# Geiger.net
KiCad netlist of a schematic drawn in EAGLE
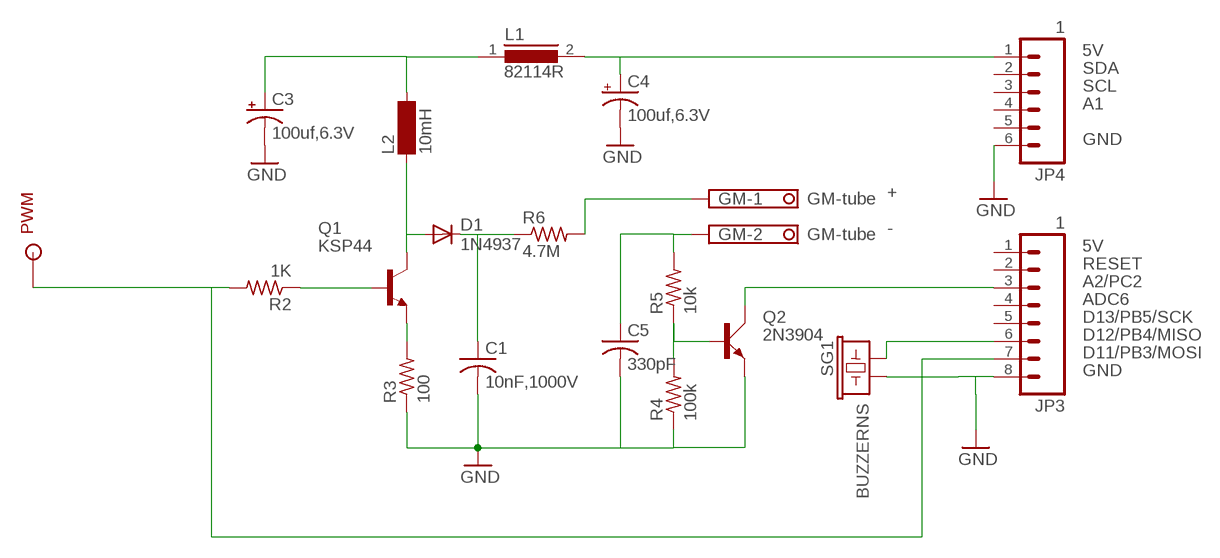
[diagram p0: schematic, sheet 1]

(export (version "E")
  (design (tool "Eeschema 10.0.6"))
  (components
    (comp (ref "C1")
      (value "10nF,1000V")
      (footprint "eagle-import:C150-054X183")
      (libsource (lib "eagle-import") (part "C-US150-054X183"))
    )
    (comp (ref "C3")
      (value "100uf,6.3V")
      (footprint "eagle-import:E2,5-7")
      (libsource (lib "eagle-import") (part "CPOL-USE2.5-7"))
    )
    (comp (ref "C4")
      (value "100uf,6.3V")
      (footprint "eagle-import:E2,5-7")
      (libsource (lib "eagle-import") (part "CPOL-USE2.5-7"))
    )
    (comp (ref "C5")
      (value "330pF")
      (footprint "eagle-import:C050-045X075")
      (libsource (lib "eagle-import") (part "C-US050-045X075"))
    )
    (comp (ref "D1")
      (value "1N4937")
      (footprint "eagle-import:DO41-10")
      (libsource (lib "eagle-import") (part "1N4933"))
    )
    (comp (ref "GM")
      (value "GM-tube")
      (footprint "eagle-import:1751248")
      (libsource (lib "eagle-import") (part "1751248"))
    )
    (comp (ref "JP3")
      (value "1")
      (footprint "eagle-import:1X08")
      (libsource (lib "eagle-import") (part "M081X08"))
    )
    (comp (ref "JP4")
      (value "1")
      (footprint "eagle-import:1X06")
      (libsource (lib "eagle-import") (part "M06SIP"))
    )
    (comp (ref "L1")
      (value "82114R")
      (footprint "eagle-import:82114R")
      (libsource (lib "eagle-import") (part "82114R"))
    )
    (comp (ref "L2")
      (value "10mH")
      (footprint "eagle-import:BS11")
      (libsource (lib "eagle-import") (part "BS11"))
    )
    (comp (ref "PWM")
      (value "SOLDER_POINTA")
      (footprint "eagle-import:P1-13")
      (libsource (lib "eagle-import") (part "SOLDER_POINTA"))
    )
    (comp (ref "Q1")
      (value "KSP44")
      (footprint "eagle-import:TO92-EBC")
      (libsource (lib "eagle-import") (part "BC550B"))
    )
    (comp (ref "Q2")
      (value "2N3904")
      (footprint "eagle-import:TO92D")
      (libsource (lib "eagle-import") (part "2N3904"))
    )
    (comp (ref "R2")
      (value "1K")
      (footprint "eagle-import:0207_10")
      (libsource (lib "eagle-import") (part "R-US_0207/10"))
    )
    (comp (ref "R3")
      (value "100")
      (footprint "eagle-import:0207_10")
      (libsource (lib "eagle-import") (part "R-US_0207/10"))
    )
    (comp (ref "R4")
      (value "100k")
      (footprint "eagle-import:0207_10")
      (libsource (lib "eagle-import") (part "R-US_0207/10"))
    )
    (comp (ref "R5")
      (value "10k")
      (footprint "eagle-import:0207_10")
      (libsource (lib "eagle-import") (part "R-US_0207/10"))
    )
    (comp (ref "R6")
      (value "4.7M")
      (footprint "eagle-import:0207_10")
      (libsource (lib "eagle-import") (part "R-US_0207/10"))
    )
    (comp (ref "SG1")
      (value "BUZZERNS")
      (footprint "eagle-import:BUZZER-12MM-NS")
      (libsource (lib "eagle-import") (part "BUZZERNS"))
    )
  )
  (nets
    (net (code "1") (name "/RESET") (class "Default")
      (node (ref "JP3") (pin "3") (pinfunction "3_3") (pintype "passive"))
      (node (ref "Q2") (pin "C") (pinfunction "C_C") (pintype "passive"))
    )
    (net (code "2") (name "GND") (class "Default")
      (node (ref "C1") (pin "2") (pinfunction "2_2") (pintype "passive"))
      (node (ref "C3") (pin "-") (pinfunction "-_-") (pintype "passive"))
      (node (ref "C4") (pin "-") (pinfunction "-_-") (pintype "passive"))
      (node (ref "C5") (pin "2") (pinfunction "2_2") (pintype "passive"))
      (node (ref "JP3") (pin "8") (pinfunction "8_8") (pintype "passive"))
      (node (ref "JP4") (pin "6") (pinfunction "6_6") (pintype "passive"))
      (node (ref "Q2") (pin "E") (pinfunction "E_E") (pintype "passive"))
      (node (ref "R3") (pin "1") (pinfunction "1_1") (pintype "passive"))
      (node (ref "R4") (pin "1") (pinfunction "1_1") (pintype "passive"))
      (node (ref "SG1") (pin "-") (pinfunction "2_-") (pintype "passive"))
    )
    (net (code "3") (name "Net-(C1-Pad1)") (class "Default")
      (node (ref "C1") (pin "1") (pinfunction "1_1") (pintype "passive"))
      (node (ref "D1") (pin "C") (pinfunction "C_C") (pintype "passive"))
      (node (ref "R6") (pin "1") (pinfunction "1_1") (pintype "passive"))
    )
    (net (code "4") (name "Net-(C3-Pad+)") (class "Default")
      (node (ref "C3") (pin "+") (pinfunction "+_+") (pintype "passive"))
      (node (ref "L1") (pin "1") (pinfunction "1_1") (pintype "passive"))
      (node (ref "L2") (pin "2") (pinfunction "2_2") (pintype "passive"))
    )
    (net (code "5") (name "Net-(C4-Pad+)") (class "Default")
      (node (ref "C4") (pin "+") (pinfunction "+_+") (pintype "passive"))
      (node (ref "JP4") (pin "1") (pinfunction "1_1") (pintype "passive"))
      (node (ref "L1") (pin "2") (pinfunction "2_2") (pintype "passive"))
    )
    (net (code "6") (name "Net-(D1-PadA)") (class "Default")
      (node (ref "D1") (pin "A") (pinfunction "A_A") (pintype "passive"))
      (node (ref "L2") (pin "1") (pinfunction "1_1") (pintype "passive"))
      (node (ref "Q1") (pin "C") (pinfunction "C_C") (pintype "passive"))
    )
    (net (code "7") (name "Net-(GMA-K)") (class "Default")
      (node (ref "GM") (pin "1") (pinfunction "K_1") (pintype "passive"))
      (node (ref "R6") (pin "2") (pinfunction "2_2") (pintype "passive"))
    )
    (net (code "8") (name "Net-(GMB-K)") (class "Default")
      (node (ref "C5") (pin "1") (pinfunction "1_1") (pintype "passive"))
      (node (ref "GM") (pin "2") (pinfunction "K_2") (pintype "passive"))
      (node (ref "R5") (pin "2") (pinfunction "2_2") (pintype "passive"))
    )
    (net (code "9") (name "Net-(PWM-P$1)") (class "Default")
      (node (ref "JP3") (pin "7") (pinfunction "7_7") (pintype "passive"))
      (node (ref "PWM") (pin "1") (pinfunction "P$1_1") (pintype "bidirectional"))
      (node (ref "R2") (pin "2") (pinfunction "2_2") (pintype "passive"))
    )
    (net (code "10") (name "Net-(Q1-PadB)") (class "Default")
      (node (ref "Q1") (pin "B") (pinfunction "B_B") (pintype "passive"))
      (node (ref "R2") (pin "1") (pinfunction "1_1") (pintype "passive"))
    )
    (net (code "11") (name "Net-(Q1-PadE)") (class "Default")
      (node (ref "Q1") (pin "E") (pinfunction "E_E") (pintype "passive"))
      (node (ref "R3") (pin "2") (pinfunction "2_2") (pintype "passive"))
    )
    (net (code "12") (name "Net-(Q2-PadB)") (class "Default")
      (node (ref "Q2") (pin "B") (pinfunction "B_B") (pintype "passive"))
      (node (ref "R4") (pin "2") (pinfunction "2_2") (pintype "passive"))
      (node (ref "R5") (pin "1") (pinfunction "1_1") (pintype "passive"))
    )
    (net (code "13") (name "Net-(SG1-1)") (class "Default")
      (node (ref "JP3") (pin "6") (pinfunction "6_6") (pintype "passive"))
      (node (ref "SG1") (pin "+") (pinfunction "1_+") (pintype "passive"))
    )
    (net (code "14") (name "unconnected-(JP3-Pad1)") (class "Default")
      (node (ref "JP3") (pin "1") (pinfunction "1_1") (pintype "passive"))
    )
    (net (code "15") (name "unconnected-(JP3-Pad2)") (class "Default")
      (node (ref "JP3") (pin "2") (pinfunction "2_2") (pintype "passive"))
    )
    (net (code "16") (name "unconnected-(JP3-Pad4)") (class "Default")
      (node (ref "JP3") (pin "4") (pinfunction "4_4") (pintype "passive"))
    )
    (net (code "17") (name "unconnected-(JP3-Pad5)") (class "Default")
      (node (ref "JP3") (pin "5") (pinfunction "5_5") (pintype "passive"))
    )
    (net (code "18") (name "unconnected-(JP4-Pad2)") (class "Default")
      (node (ref "JP4") (pin "2") (pinfunction "2_2") (pintype "passive"))
    )
    (net (code "19") (name "unconnected-(JP4-Pad3)") (class "Default")
      (node (ref "JP4") (pin "3") (pinfunction "3_3") (pintype "passive"))
    )
    (net (code "20") (name "unconnected-(JP4-Pad4)") (class "Default")
      (node (ref "JP4") (pin "4") (pinfunction "4_4") (pintype "passive"))
    )
    (net (code "21") (name "unconnected-(JP4-Pad5)") (class "Default")
      (node (ref "JP4") (pin "5") (pinfunction "5_5") (pintype "passive"))
    )
  )
)
